# test-shield.net
KiCad netlist of a schematic drawn in EAGLE
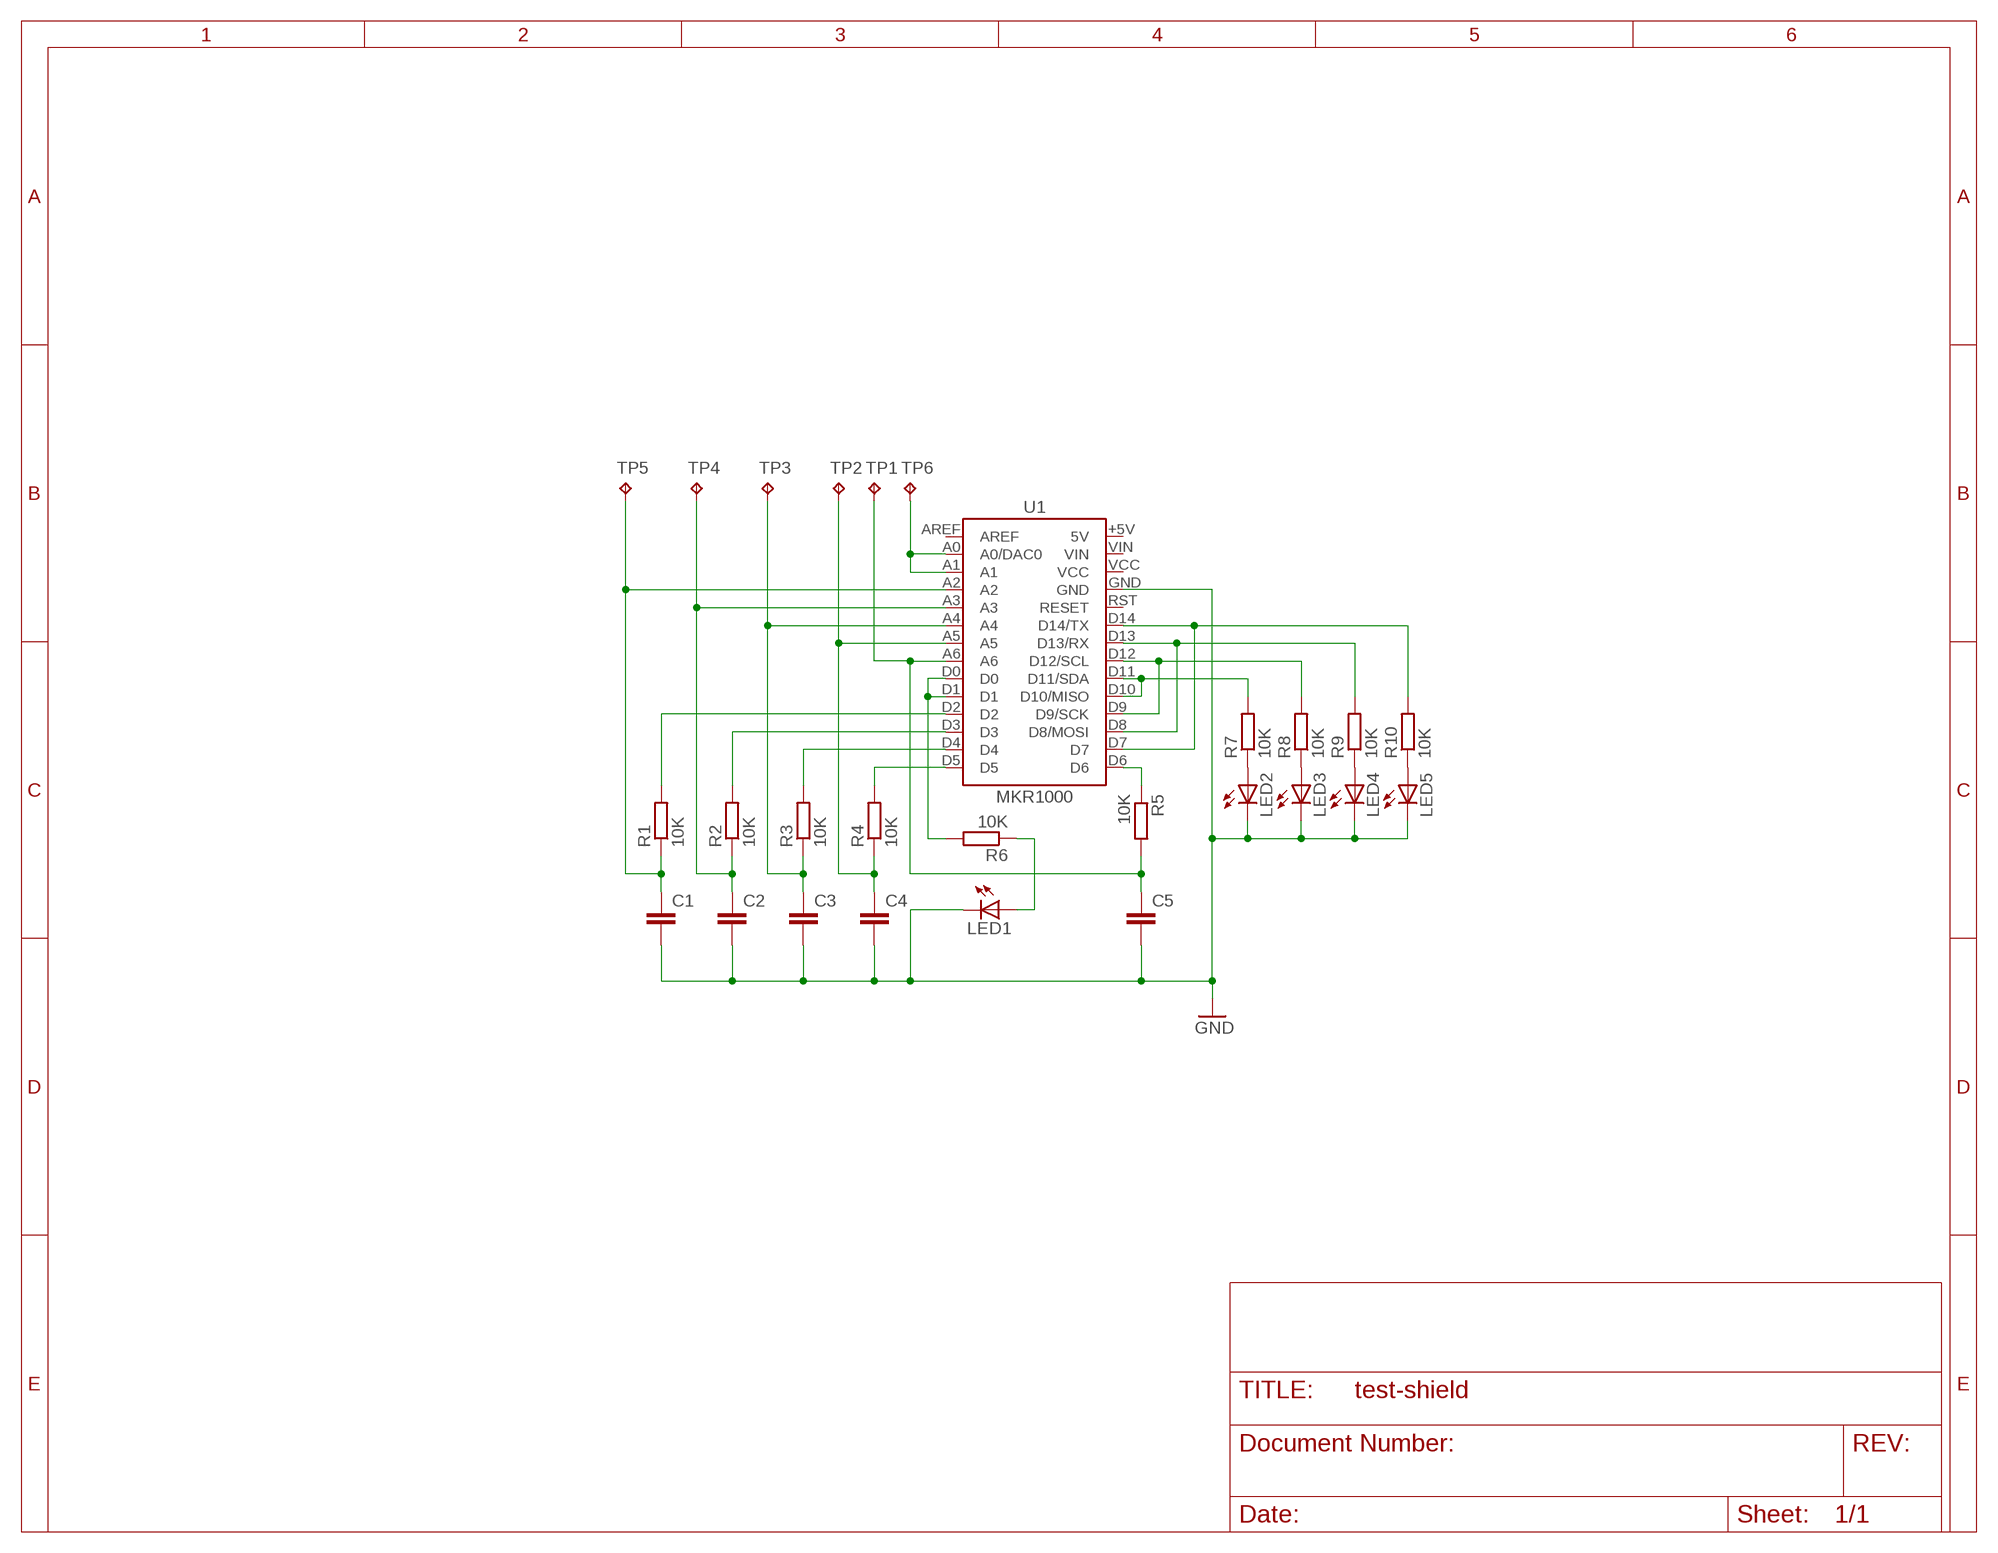
[diagram p0: schematic, sheet 1]

(export (version "E")
  (design (tool "Eeschema 10.0.6"))
  (components
    (comp (ref "C1")
      (value "C-EUC0603")
      (footprint "eagle-import:C0603")
      (libsource (lib "eagle-import") (part "C-EUC0603"))
    )
    (comp (ref "C2")
      (value "C-EUC0603")
      (footprint "eagle-import:C0603")
      (libsource (lib "eagle-import") (part "C-EUC0603"))
    )
    (comp (ref "C3")
      (value "C-EUC0603")
      (footprint "eagle-import:C0603")
      (libsource (lib "eagle-import") (part "C-EUC0603"))
    )
    (comp (ref "C4")
      (value "C-EUC0603")
      (footprint "eagle-import:C0603")
      (libsource (lib "eagle-import") (part "C-EUC0603"))
    )
    (comp (ref "C5")
      (value "C-EUC0603")
      (footprint "eagle-import:C0603")
      (libsource (lib "eagle-import") (part "C-EUC0603"))
    )
    (comp (ref "LED1")
      (value "LEDCHIPLED_0805")
      (footprint "eagle-import:CHIPLED_0805")
      (libsource (lib "eagle-import") (part "LEDCHIPLED_0805"))
    )
    (comp (ref "LED2")
      (value "LEDCHIPLED_0805")
      (footprint "eagle-import:CHIPLED_0805")
      (libsource (lib "eagle-import") (part "LEDCHIPLED_0805"))
    )
    (comp (ref "LED3")
      (value "LEDCHIPLED_0805")
      (footprint "eagle-import:CHIPLED_0805")
      (libsource (lib "eagle-import") (part "LEDCHIPLED_0805"))
    )
    (comp (ref "LED4")
      (value "LEDCHIPLED_0805")
      (footprint "eagle-import:CHIPLED_0805")
      (libsource (lib "eagle-import") (part "LEDCHIPLED_0805"))
    )
    (comp (ref "LED5")
      (value "LEDCHIPLED_0805")
      (footprint "eagle-import:CHIPLED_0805")
      (libsource (lib "eagle-import") (part "LEDCHIPLED_0805"))
    )
    (comp (ref "R1")
      (value "10K")
      (footprint "eagle-import:R0603")
      (libsource (lib "eagle-import") (part "R-EU_R0603"))
    )
    (comp (ref "R2")
      (value "10K")
      (footprint "eagle-import:R0603")
      (libsource (lib "eagle-import") (part "R-EU_R0603"))
    )
    (comp (ref "R3")
      (value "10K")
      (footprint "eagle-import:R0603")
      (libsource (lib "eagle-import") (part "R-EU_R0603"))
    )
    (comp (ref "R4")
      (value "10K")
      (footprint "eagle-import:R0603")
      (libsource (lib "eagle-import") (part "R-EU_R0603"))
    )
    (comp (ref "R5")
      (value "10K")
      (footprint "eagle-import:R0603")
      (libsource (lib "eagle-import") (part "R-EU_R0603"))
    )
    (comp (ref "R6")
      (value "10K")
      (footprint "eagle-import:R0603")
      (libsource (lib "eagle-import") (part "R-EU_R0603"))
    )
    (comp (ref "R7")
      (value "10K")
      (footprint "eagle-import:R0603")
      (libsource (lib "eagle-import") (part "R-EU_R0603"))
    )
    (comp (ref "R8")
      (value "10K")
      (footprint "eagle-import:R0603")
      (libsource (lib "eagle-import") (part "R-EU_R0603"))
    )
    (comp (ref "R9")
      (value "10K")
      (footprint "eagle-import:R0603")
      (libsource (lib "eagle-import") (part "R-EU_R0603"))
    )
    (comp (ref "R10")
      (value "10K")
      (footprint "eagle-import:R0603")
      (libsource (lib "eagle-import") (part "R-EU_R0603"))
    )
    (comp (ref "TP1")
      (value "TPPAD1-13")
      (footprint "eagle-import:P1-13")
      (libsource (lib "eagle-import") (part "TPPAD1-13"))
    )
    (comp (ref "TP2")
      (value "TPPAD1-13")
      (footprint "eagle-import:P1-13")
      (libsource (lib "eagle-import") (part "TPPAD1-13"))
    )
    (comp (ref "TP3")
      (value "TPPAD1-13")
      (footprint "eagle-import:P1-13")
      (libsource (lib "eagle-import") (part "TPPAD1-13"))
    )
    (comp (ref "TP4")
      (value "TPPAD1-13")
      (footprint "eagle-import:P1-13")
      (libsource (lib "eagle-import") (part "TPPAD1-13"))
    )
    (comp (ref "TP5")
      (value "TPPAD1-13")
      (footprint "eagle-import:P1-13")
      (libsource (lib "eagle-import") (part "TPPAD1-13"))
    )
    (comp (ref "TP6")
      (value "TPPAD1-13")
      (footprint "eagle-import:P1-13")
      (libsource (lib "eagle-import") (part "TPPAD1-13"))
    )
    (comp (ref "U1")
      (value "MKR1000")
      (footprint "eagle-import:MKR1000-THRU-HOLE")
      (libsource (lib "eagle-import") (part "MKR1000"))
    )
  )
  (nets
    (net (code "1") (name "GND") (class "Default")
      (node (ref "C1") (pin "2") (pinfunction "2_2") (pintype "passive"))
      (node (ref "C2") (pin "2") (pinfunction "2_2") (pintype "passive"))
      (node (ref "C3") (pin "2") (pinfunction "2_2") (pintype "passive"))
      (node (ref "C4") (pin "2") (pinfunction "2_2") (pintype "passive"))
      (node (ref "C5") (pin "2") (pinfunction "2_2") (pintype "passive"))
      (node (ref "LED1") (pin "C") (pinfunction "C_C") (pintype "passive"))
      (node (ref "LED2") (pin "C") (pinfunction "C_C") (pintype "passive"))
      (node (ref "LED3") (pin "C") (pinfunction "C_C") (pintype "passive"))
      (node (ref "LED4") (pin "C") (pinfunction "C_C") (pintype "passive"))
      (node (ref "LED5") (pin "C") (pinfunction "C_C") (pintype "passive"))
      (node (ref "U1") (pin "GND") (pinfunction "GND_GND") (pintype "bidirectional"))
    )
    (net (code "2") (name "Net-(C1-Pad1)") (class "Default")
      (node (ref "C1") (pin "1") (pinfunction "1_1") (pintype "passive"))
      (node (ref "R1") (pin "1") (pinfunction "1_1") (pintype "passive"))
      (node (ref "TP5") (pin "TP") (pinfunction "TP_TP") (pintype "input"))
      (node (ref "U1") (pin "A2") (pinfunction "A2_A2") (pintype "bidirectional"))
    )
    (net (code "3") (name "Net-(C2-Pad1)") (class "Default")
      (node (ref "C2") (pin "1") (pinfunction "1_1") (pintype "passive"))
      (node (ref "R2") (pin "1") (pinfunction "1_1") (pintype "passive"))
      (node (ref "TP4") (pin "TP") (pinfunction "TP_TP") (pintype "input"))
      (node (ref "U1") (pin "A3") (pinfunction "A3_A3") (pintype "bidirectional"))
    )
    (net (code "4") (name "Net-(C3-Pad1)") (class "Default")
      (node (ref "C3") (pin "1") (pinfunction "1_1") (pintype "passive"))
      (node (ref "R3") (pin "1") (pinfunction "1_1") (pintype "passive"))
      (node (ref "TP3") (pin "TP") (pinfunction "TP_TP") (pintype "input"))
      (node (ref "U1") (pin "A4") (pinfunction "A4_A4") (pintype "bidirectional"))
    )
    (net (code "5") (name "Net-(C4-Pad1)") (class "Default")
      (node (ref "C4") (pin "1") (pinfunction "1_1") (pintype "passive"))
      (node (ref "R4") (pin "1") (pinfunction "1_1") (pintype "passive"))
      (node (ref "TP2") (pin "TP") (pinfunction "TP_TP") (pintype "input"))
      (node (ref "U1") (pin "A5") (pinfunction "A5_A5") (pintype "bidirectional"))
    )
    (net (code "6") (name "Net-(C5-Pad1)") (class "Default")
      (node (ref "C5") (pin "1") (pinfunction "1_1") (pintype "passive"))
      (node (ref "R5") (pin "2") (pinfunction "2_2") (pintype "passive"))
      (node (ref "TP1") (pin "TP") (pinfunction "TP_TP") (pintype "input"))
      (node (ref "U1") (pin "A6") (pinfunction "A6_A6") (pintype "bidirectional"))
    )
    (net (code "7") (name "Net-(LED1-PadA)") (class "Default")
      (node (ref "LED1") (pin "A") (pinfunction "A_A") (pintype "passive"))
      (node (ref "R6") (pin "1") (pinfunction "1_1") (pintype "passive"))
    )
    (net (code "8") (name "Net-(LED2-PadA)") (class "Default")
      (node (ref "LED2") (pin "A") (pinfunction "A_A") (pintype "passive"))
      (node (ref "R7") (pin "1") (pinfunction "1_1") (pintype "passive"))
    )
    (net (code "9") (name "Net-(LED3-PadA)") (class "Default")
      (node (ref "LED3") (pin "A") (pinfunction "A_A") (pintype "passive"))
      (node (ref "R8") (pin "1") (pinfunction "1_1") (pintype "passive"))
    )
    (net (code "10") (name "Net-(LED4-PadA)") (class "Default")
      (node (ref "LED4") (pin "A") (pinfunction "A_A") (pintype "passive"))
      (node (ref "R9") (pin "1") (pinfunction "1_1") (pintype "passive"))
    )
    (net (code "11") (name "Net-(LED5-PadA)") (class "Default")
      (node (ref "LED5") (pin "A") (pinfunction "A_A") (pintype "passive"))
      (node (ref "R10") (pin "1") (pinfunction "1_1") (pintype "passive"))
    )
    (net (code "12") (name "Net-(R1-Pad2)") (class "Default")
      (node (ref "R1") (pin "2") (pinfunction "2_2") (pintype "passive"))
      (node (ref "U1") (pin "D2") (pinfunction "D2_D2") (pintype "bidirectional"))
    )
    (net (code "13") (name "Net-(R2-Pad2)") (class "Default")
      (node (ref "R2") (pin "2") (pinfunction "2_2") (pintype "passive"))
      (node (ref "U1") (pin "D3") (pinfunction "D3_D3") (pintype "bidirectional"))
    )
    (net (code "14") (name "Net-(R3-Pad2)") (class "Default")
      (node (ref "R3") (pin "2") (pinfunction "2_2") (pintype "passive"))
      (node (ref "U1") (pin "D4") (pinfunction "D4_D4") (pintype "bidirectional"))
    )
    (net (code "15") (name "Net-(R4-Pad2)") (class "Default")
      (node (ref "R4") (pin "2") (pinfunction "2_2") (pintype "passive"))
      (node (ref "U1") (pin "D5") (pinfunction "D5_D5") (pintype "bidirectional"))
    )
    (net (code "16") (name "Net-(R5-Pad1)") (class "Default")
      (node (ref "R5") (pin "1") (pinfunction "1_1") (pintype "passive"))
      (node (ref "U1") (pin "D6") (pinfunction "D6_D6") (pintype "bidirectional"))
    )
    (net (code "17") (name "Net-(R6-Pad2)") (class "Default")
      (node (ref "R6") (pin "2") (pinfunction "2_2") (pintype "passive"))
      (node (ref "U1") (pin "D0") (pinfunction "D0_D0") (pintype "bidirectional"))
      (node (ref "U1") (pin "D1") (pinfunction "D1_D1") (pintype "bidirectional"))
    )
    (net (code "18") (name "Net-(U1-A0{slash}DAC0)") (class "Default")
      (node (ref "TP6") (pin "TP") (pinfunction "TP_TP") (pintype "input"))
      (node (ref "U1") (pin "A0") (pinfunction "A0/DAC0_A0") (pintype "bidirectional"))
      (node (ref "U1") (pin "A1") (pinfunction "A1_A1") (pintype "bidirectional"))
    )
    (net (code "19") (name "Net-(U1-D10{slash}MISO)") (class "Default")
      (node (ref "R7") (pin "2") (pinfunction "2_2") (pintype "passive"))
      (node (ref "U1") (pin "D10") (pinfunction "D10/MISO_D10") (pintype "bidirectional"))
      (node (ref "U1") (pin "D11") (pinfunction "D11/SDA_D11") (pintype "bidirectional"))
    )
    (net (code "20") (name "Net-(U1-D12{slash}SCL)") (class "Default")
      (node (ref "R8") (pin "2") (pinfunction "2_2") (pintype "passive"))
      (node (ref "U1") (pin "D12") (pinfunction "D12/SCL_D12") (pintype "bidirectional"))
      (node (ref "U1") (pin "D9") (pinfunction "D9/SCK_D9") (pintype "bidirectional"))
    )
    (net (code "21") (name "Net-(U1-D13{slash}RX)") (class "Default")
      (node (ref "R9") (pin "2") (pinfunction "2_2") (pintype "passive"))
      (node (ref "U1") (pin "D13") (pinfunction "D13/RX_D13") (pintype "bidirectional"))
      (node (ref "U1") (pin "D8") (pinfunction "D8/MOSI_D8") (pintype "bidirectional"))
    )
    (net (code "22") (name "Net-(U1-D14{slash}TX)") (class "Default")
      (node (ref "R10") (pin "2") (pinfunction "2_2") (pintype "passive"))
      (node (ref "U1") (pin "D14") (pinfunction "D14/TX_D14") (pintype "bidirectional"))
      (node (ref "U1") (pin "D7") (pinfunction "D7_D7") (pintype "bidirectional"))
    )
    (net (code "23") (name "unconnected-(U1-5V-Pad+5V)") (class "Default")
      (node (ref "U1") (pin "+5V") (pinfunction "5V_+5V") (pintype "bidirectional"))
    )
    (net (code "24") (name "unconnected-(U1-PadAREF)") (class "Default")
      (node (ref "U1") (pin "AREF") (pinfunction "AREF_AREF") (pintype "bidirectional"))
    )
    (net (code "25") (name "unconnected-(U1-PadVCC)") (class "Default")
      (node (ref "U1") (pin "VCC") (pinfunction "VCC_VCC") (pintype "bidirectional"))
    )
    (net (code "26") (name "unconnected-(U1-PadVIN)") (class "Default")
      (node (ref "U1") (pin "VIN") (pinfunction "VIN_VIN") (pintype "bidirectional"))
    )
    (net (code "27") (name "unconnected-(U1-RESET-PadRST)") (class "Default")
      (node (ref "U1") (pin "RST") (pinfunction "RESET_RST") (pintype "bidirectional"))
    )
  )
)
